# PowerSupply.net
KiCad netlist of a schematic drawn in Altium Designer
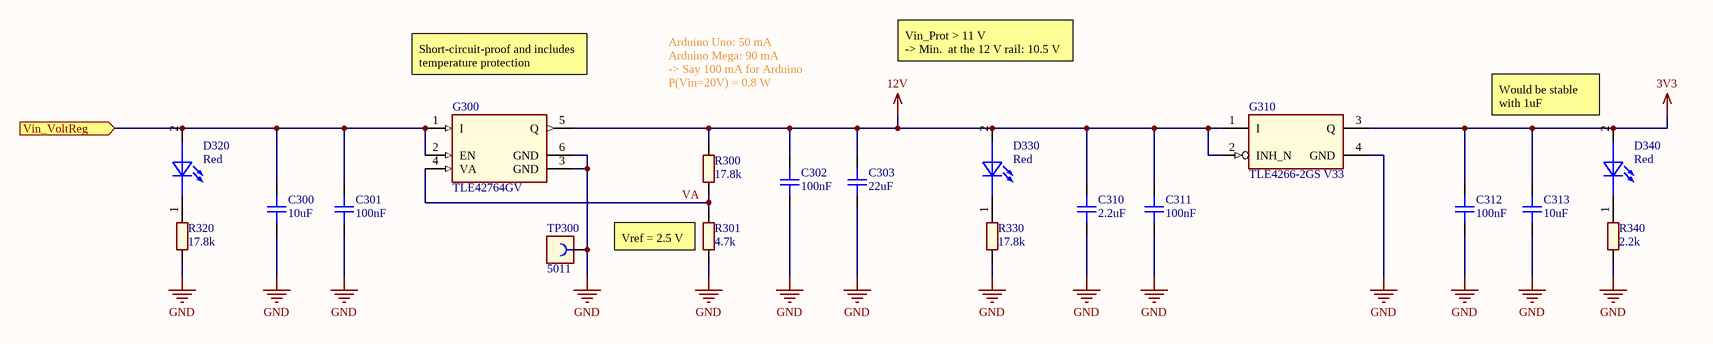
[diagram p0: PowerSupply.SchDoc]

(export (version "E")
  (design (tool "Eeschema 10.0.6"))
  (components
    (comp (ref "C300")
      (value "10uF")
      (footprint "CAPC3216X190N-1")
      (description "CAP / CERA / 10uF / 50V / 20% / X5R (EIA) / -55°C to 85°C / 1206 (3216) / SMD / -")
      (fields (field (name "MANUFACTURER") "Taiyo Yuden"))
      (libsource (lib "PCBLibraryData") (part "CAP-SGL-STD-02P_00000001"))
    )
    (comp (ref "C301")
      (value "100nF")
      (footprint "CAPC1608X90N-2")
      (description "CAP / CERA / 100nF / 50V / 10% / X7R (EIA) / -55°C to 125°C / 0603 / SMD / -")
      (fields (field (name "MANUFACTURER") "AVX"))
      (libsource (lib "PCBLibraryData") (part "CAP-SGL-STD-02P_00000001"))
    )
    (comp (ref "C302")
      (value "100nF")
      (footprint "CAPC1608X90N-2")
      (description "CAP / CERA / 100nF / 50V / 10% / X7R (EIA) / -55°C to 125°C / 0603 / SMD / -")
      (fields (field (name "MANUFACTURER") "AVX"))
      (libsource (lib "PCBLibraryData") (part "CAP-SGL-STD-02P_00000001"))
    )
    (comp (ref "C303")
      (value "22uF")
      (footprint "CAPC3225X270N-0")
      (description "CAP / CERA / 22uF / 25V / 10% / X5R (EIA) / -55°C to 85°C / 1210(3225) / SMD / -")
      (fields (field (name "MANUFACTURER") "Taiyo Yuden"))
      (libsource (lib "PCBLibraryData") (part "CAP-SGL-STD-02P_00000001"))
    )
    (comp (ref "C310")
      (value "2.2uF")
      (footprint "CAPC1608X90N-3")
      (description "CAP / CERA / 2.2uF / 25V / 10% / X5R (EIA) / -55°C to 85°C / 0603(1608) / SMD / -")
      (fields (field (name "LEGACY PARTNUMBER") "CAP01010924") (field (name "MANUFACTURER") "MuRata"))
      (libsource (lib "PCBLibraryData") (part "CAP-SGL-STD-02P_00000001"))
    )
    (comp (ref "C311")
      (value "100nF")
      (footprint "CAPC1608X90N-2")
      (description "CAP / CERA / 100nF / 50V / 10% / X7R (EIA) / -55°C to 125°C / 0603 / SMD / -")
      (fields (field (name "MANUFACTURER") "AVX"))
      (libsource (lib "PCBLibraryData") (part "CAP-SGL-STD-02P_00000001"))
    )
    (comp (ref "C312")
      (value "100nF")
      (footprint "CAPC1608X90N-2")
      (description "CAP / CERA / 100nF / 50V / 10% / X7R (EIA) / -55°C to 125°C / 0603 / SMD / -")
      (fields (field (name "MANUFACTURER") "AVX"))
      (libsource (lib "PCBLibraryData") (part "CAP-SGL-STD-02P_00000001"))
    )
    (comp (ref "C313")
      (value "10uF")
      (footprint "CAPC3216X190N-1")
      (description "CAP / CERA / 10uF / 50V / 20% / X5R (EIA) / -55°C to 85°C / 1206 (3216) / SMD / -")
      (fields (field (name "MANUFACTURER") "Taiyo Yuden"))
      (libsource (lib "PCBLibraryData") (part "CAP-SGL-STD-02P_00000001"))
    )
    (comp (ref "D320")
      (value "Red")
      (footprint "LEDSC160X80X80-2N-1")
      (description "WL-SMCW SMT Mono-color Chip LED Waterclear, Red,630nm")
      (fields (field (name "MANUFACTURER") "Wurth Elektronik"))
      (libsource (lib "PCBLibraryData") (part "d_led_a"))
    )
    (comp (ref "D330")
      (value "Red")
      (footprint "LEDSC160X80X80-2N-1")
      (description "WL-SMCW SMT Mono-color Chip LED Waterclear, Red,630nm")
      (fields (field (name "MANUFACTURER") "Wurth Elektronik"))
      (libsource (lib "PCBLibraryData") (part "d_led_a"))
    )
    (comp (ref "D340")
      (value "Red")
      (footprint "LEDSC160X80X80-2N-1")
      (description "WL-SMCW SMT Mono-color Chip LED Waterclear, Red,630nm")
      (fields (field (name "MANUFACTURER") "Wurth Elektronik"))
      (libsource (lib "PCBLibraryData") (part "d_led_a"))
    )
    (comp (ref "G300")
      (value "TLE42764GV")
      (footprint "TO170P1500X450-6N-V")
      (description "Monolithic integrated low dropout voltage regulator")
      (fields (field (name "MANUFACTURER") "Infineon Technologies"))
      (libsource (lib "PCBLibraryData") (part "TLE42764GV"))
    )
    (comp (ref "G310")
      (value "TLE4266-2GS V33")
      (footprint "SOT230P700X180-4N-3")
      (description "Low Drop Voltage Regulator for 3.3V Fixed Output Voltage")
      (fields (field (name "MANUFACTURER") "Infineon Technologies"))
      (libsource (lib "PCBLibraryData") (part "TLE_4266-2"))
    )
    (comp (ref "R300")
      (value "17.8k")
      (footprint "RESC1609X50N")
      (description "RES / STD / 17.8k / 100mW / 1% / 100ppm/K / -55°C to 155°C / 0603 / SMD / -")
      (fields (field (name "LEGACY PARTNUMBER") "RES01801283") (field (name "MANUFACTURER") "Vishay"))
      (libsource (lib "PCBLibraryData") (part "RES-SGL-STD-02P_00000006"))
    )
    (comp (ref "R301")
      (value "4.7k")
      (footprint "RESC1609X50N")
      (description "RES / STD / 4.7k / 100mW / 1% / 100ppm/K / -55°C to 155°C / 0603 / SMD / -")
      (fields (field (name "LEGACY PARTNUMBER") "RES01801219") (field (name "MANUFACTURER") "Vishay"))
      (libsource (lib "PCBLibraryData") (part "RES-SGL-STD-02P_00000006"))
    )
    (comp (ref "R320")
      (value "17.8k")
      (footprint "RESC1609X50N")
      (description "RES / STD / 17.8k / 100mW / 1% / 100ppm/K / -55°C to 155°C / 0603 / SMD / -")
      (fields (field (name "LEGACY PARTNUMBER") "RES01801283") (field (name "MANUFACTURER") "Vishay"))
      (libsource (lib "PCBLibraryData") (part "RES-SGL-STD-02P_00000006"))
    )
    (comp (ref "R330")
      (value "17.8k")
      (footprint "RESC1609X50N")
      (description "RES / STD / 17.8k / 100mW / 1% / 100ppm/K / -55°C to 155°C / 0603 / SMD / -")
      (fields (field (name "LEGACY PARTNUMBER") "RES01801283") (field (name "MANUFACTURER") "Vishay"))
      (libsource (lib "PCBLibraryData") (part "RES-SGL-STD-02P_00000006"))
    )
    (comp (ref "R340")
      (value "2.2k")
      (footprint "RESC1609X50N")
      (description "RES / STD / 2.2k / 100mW / 1% / 100ppm/K / -55°C to 155°C / 0603 / SMD / -")
      (fields (field (name "LEGACY PARTNUMBER") "RES01801179") (field (name "MANUFACTURER") "Vishay"))
      (libsource (lib "PCBLibraryData") (part "RES-SGL-STD-02P_00000006"))
    )
    (comp (ref "TP300")
      (value "5011")
      (footprint "CON-THT-TP-5011")
      (description "PC Test Point-Multipurpose THT, Black")
      (fields
        (field (name "LEGACY PARTNUMBER") "CON01500530")
        (field (name "MANUFACTURER") "Keystone Electronics Corp.")
      )
      (libsource (lib "PCBLibraryData") (part "connector_1_f"))
    )
  )
  (nets
    (net (code "1") (name "/VA") (class "Default")
      (node (ref "G300") (pin "4") (pinfunction "VA_4") (pintype "input"))
      (node (ref "R300") (pin "1") (pinfunction "1_1") (pintype "passive"))
      (node (ref "R301") (pin "2") (pinfunction "2_2") (pintype "passive"))
    )
    (net (code "2") (name "/Vin_VoltReg") (class "Default")
      (node (ref "C300") (pin "2") (pinfunction "2_2") (pintype "passive"))
      (node (ref "C301") (pin "2") (pinfunction "2_2") (pintype "passive"))
      (node (ref "D320") (pin "2") (pinfunction "Anode_2") (pintype "passive"))
      (node (ref "G300") (pin "1") (pinfunction "I_1") (pintype "input"))
      (node (ref "G300") (pin "2") (pinfunction "EN_2") (pintype "input"))
    )
    (net (code "3") (name "3V3") (class "Default")
      (node (ref "C312") (pin "2") (pinfunction "2_2") (pintype "passive"))
      (node (ref "C313") (pin "2") (pinfunction "2_2") (pintype "passive"))
      (node (ref "D340") (pin "2") (pinfunction "Anode_2") (pintype "passive"))
      (node (ref "G310") (pin "3") (pinfunction "Q_3") (pintype "power_in"))
    )
    (net (code "4") (name "12V") (class "Default")
      (node (ref "C302") (pin "2") (pinfunction "2_2") (pintype "passive"))
      (node (ref "C303") (pin "2") (pinfunction "2_2") (pintype "passive"))
      (node (ref "C310") (pin "2") (pinfunction "2_2") (pintype "passive"))
      (node (ref "C311") (pin "2") (pinfunction "2_2") (pintype "passive"))
      (node (ref "D330") (pin "2") (pinfunction "Anode_2") (pintype "passive"))
      (node (ref "G300") (pin "5") (pinfunction "Q_5") (pintype "output"))
      (node (ref "G310") (pin "1") (pinfunction "I_1") (pintype "power_in"))
      (node (ref "G310") (pin "2") (pinfunction "INH_N_2") (pintype "input"))
      (node (ref "R300") (pin "2") (pinfunction "2_2") (pintype "passive"))
    )
    (net (code "5") (name "GND") (class "Default")
      (node (ref "C300") (pin "1") (pinfunction "1_1") (pintype "passive"))
      (node (ref "C301") (pin "1") (pinfunction "1_1") (pintype "passive"))
      (node (ref "C302") (pin "1") (pinfunction "1_1") (pintype "passive"))
      (node (ref "C303") (pin "1") (pinfunction "1_1") (pintype "passive"))
      (node (ref "C310") (pin "1") (pinfunction "1_1") (pintype "passive"))
      (node (ref "C311") (pin "1") (pinfunction "1_1") (pintype "passive"))
      (node (ref "C312") (pin "1") (pinfunction "1_1") (pintype "passive"))
      (node (ref "C313") (pin "1") (pinfunction "1_1") (pintype "passive"))
      (node (ref "G300") (pin "3") (pinfunction "GND_3") (pintype "power_in"))
      (node (ref "G300") (pin "6") (pinfunction "GND_6") (pintype "power_in"))
      (node (ref "G310") (pin "4") (pinfunction "GND_4") (pintype "power_in"))
      (node (ref "R301") (pin "1") (pinfunction "1_1") (pintype "passive"))
      (node (ref "R320") (pin "1") (pinfunction "1_1") (pintype "passive"))
      (node (ref "R330") (pin "1") (pinfunction "1_1") (pintype "passive"))
      (node (ref "R340") (pin "1") (pinfunction "1_1") (pintype "passive"))
      (node (ref "TP300") (pin "1") (pinfunction "1_1") (pintype "passive"))
    )
    (net (code "6") (name "Net-(D320-Cathode)") (class "Default")
      (node (ref "D320") (pin "1") (pinfunction "Cathode_1") (pintype "passive"))
      (node (ref "R320") (pin "2") (pinfunction "2_2") (pintype "passive"))
    )
    (net (code "7") (name "Net-(D330-Cathode)") (class "Default")
      (node (ref "D330") (pin "1") (pinfunction "Cathode_1") (pintype "passive"))
      (node (ref "R330") (pin "2") (pinfunction "2_2") (pintype "passive"))
    )
    (net (code "8") (name "Net-(D340-Cathode)") (class "Default")
      (node (ref "D340") (pin "1") (pinfunction "Cathode_1") (pintype "passive"))
      (node (ref "R340") (pin "2") (pinfunction "2_2") (pintype "passive"))
    )
  )
)
